# design.net
KiCad netlist of a schematic drawn in EasyEDA Pro
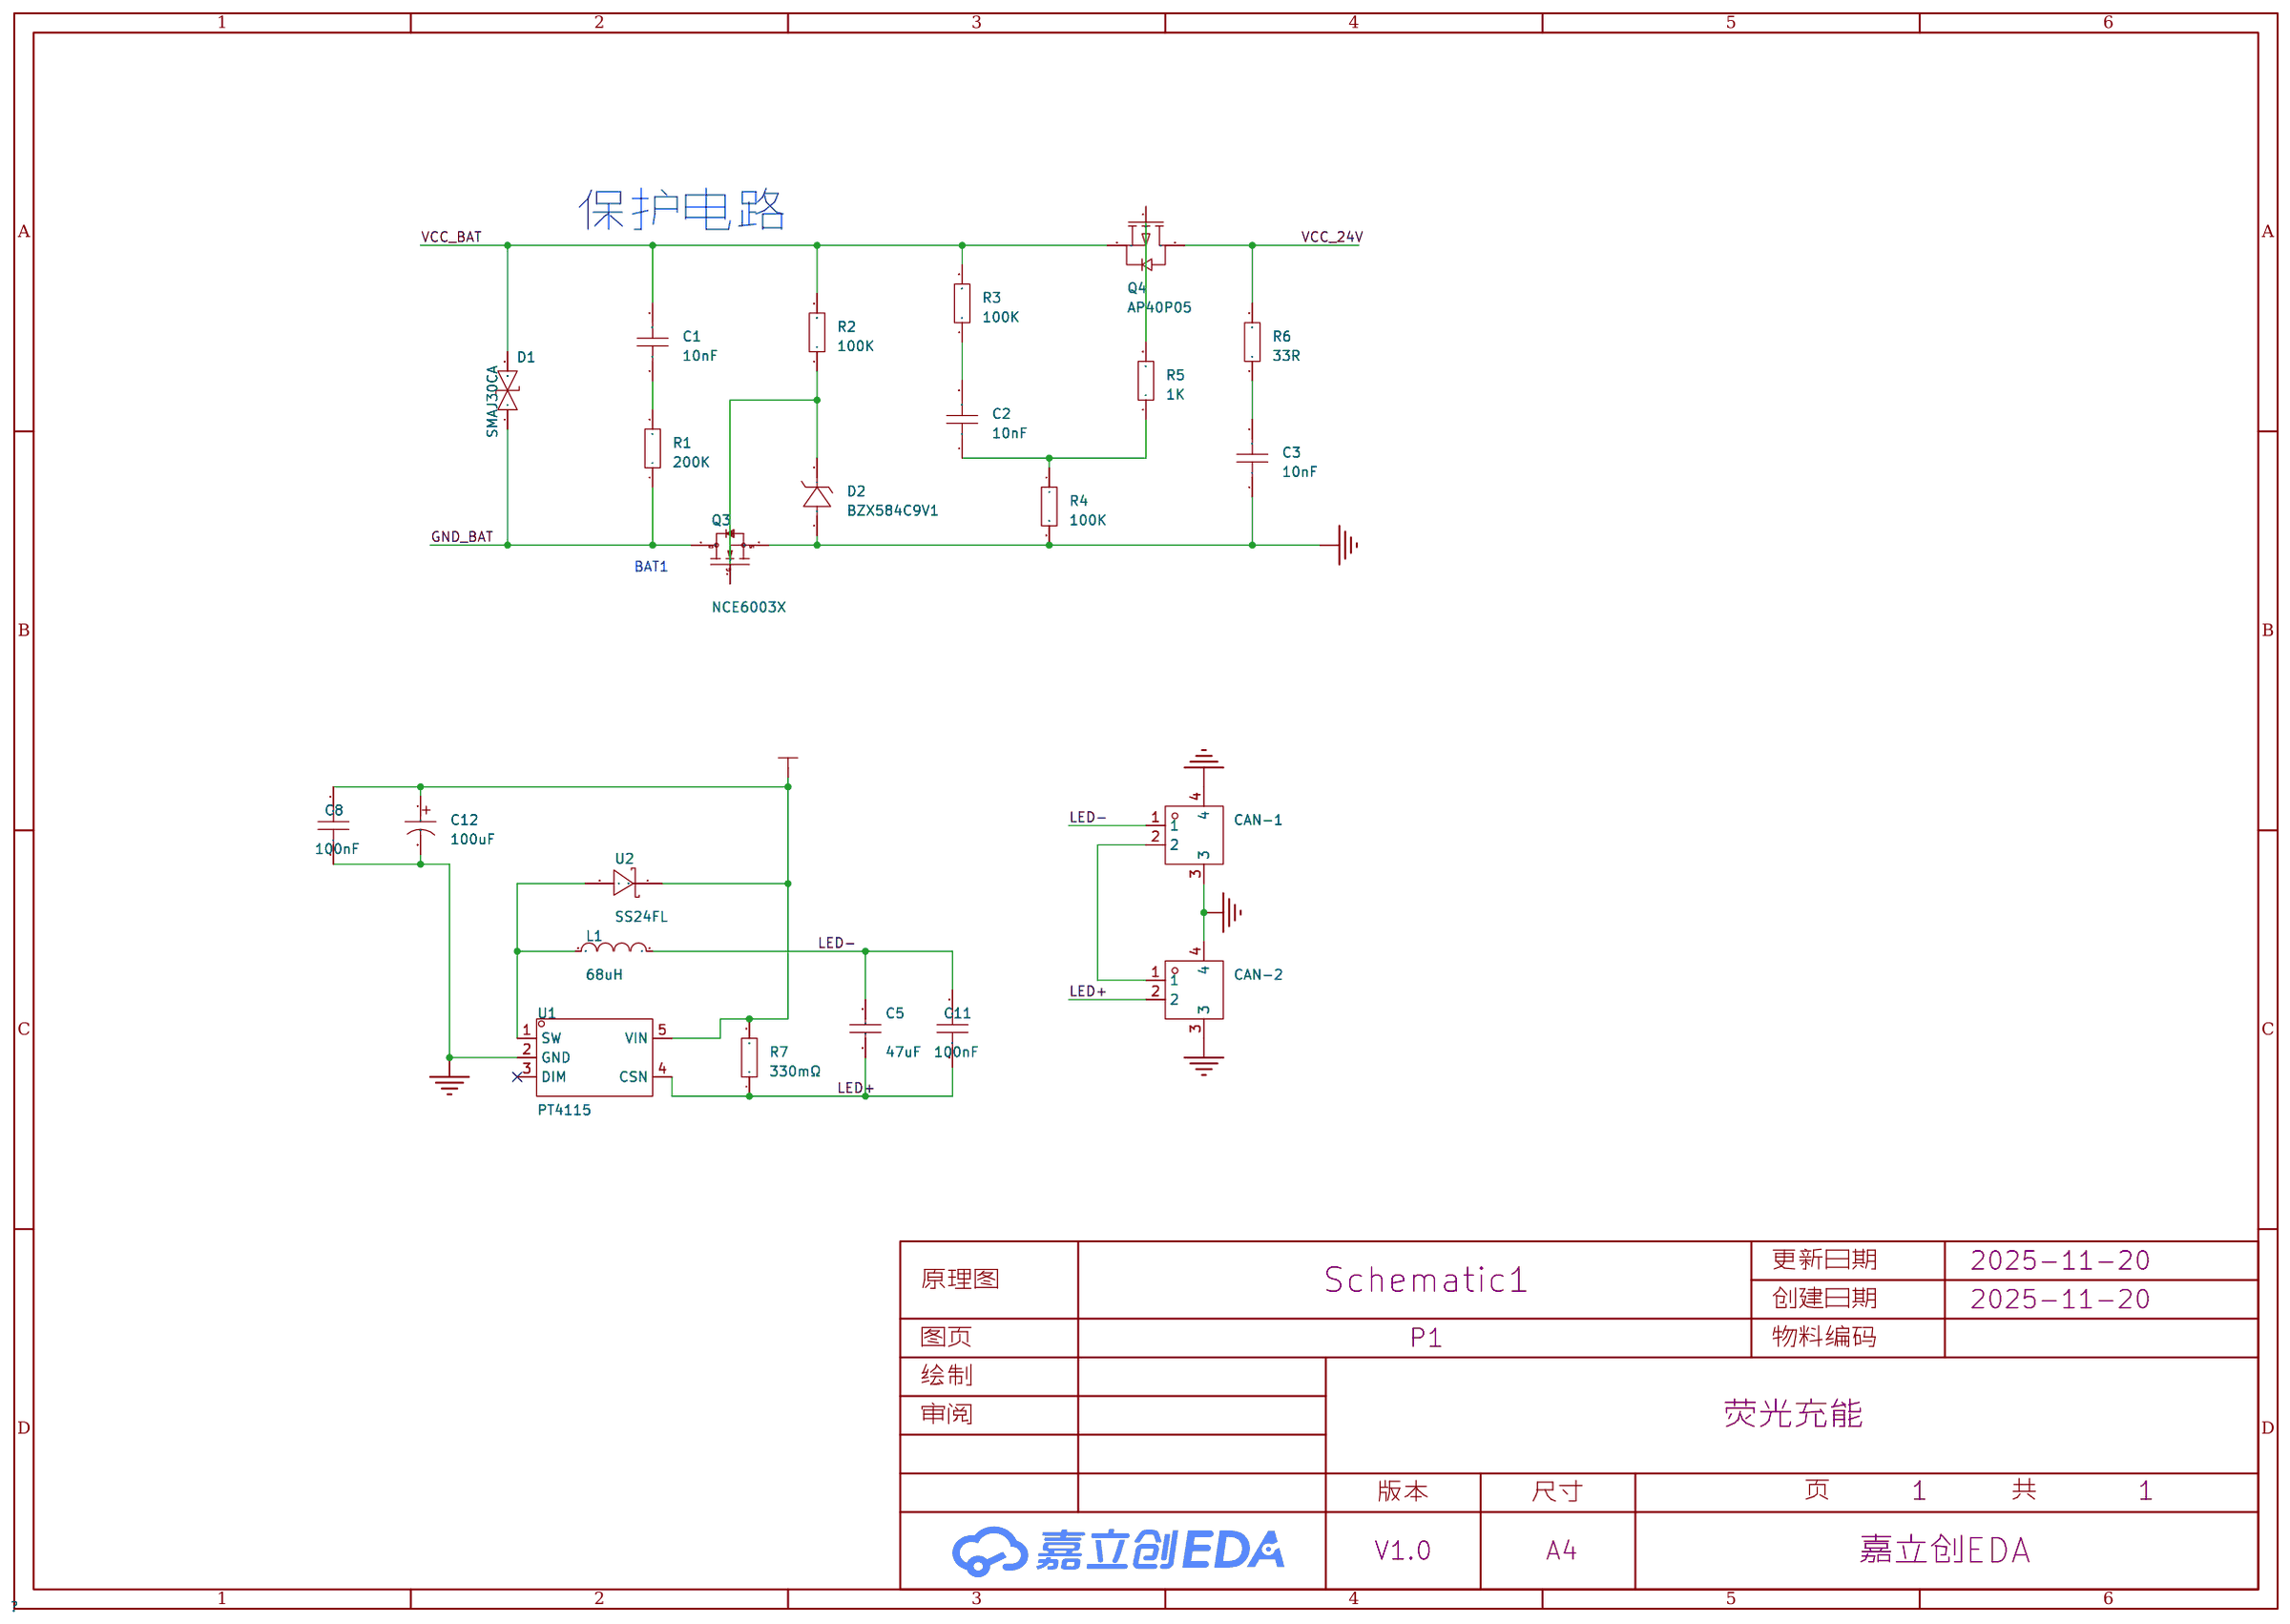
[diagram p0: schematic sheet]

(export (version "E")
  (design (tool "Eeschema 10.0.6"))
  (components
    (comp (ref "C1")
      (value "10nF")
      (footprint "easyedapro:C0603")
      (libsource (lib "easyedapro") (part "CapAcitance"))
    )
    (comp (ref "C2")
      (value "10nF")
      (footprint "easyedapro:C0603")
      (libsource (lib "easyedapro") (part "CapAcitance"))
    )
    (comp (ref "C3")
      (value "10nF")
      (footprint "easyedapro:C0603")
      (libsource (lib "easyedapro") (part "CapAcitance"))
    )
    (comp (ref "C5")
      (value "47uF")
      (footprint "easyedapro:C0805")
      (description "容值:1uF;精度:±10%;额定电压:50V;材质(温度系数):X7R;")
      (fields
        (field (name "Manufacturer Part") "CL21B105KBFNNNE")
        (field (name "Manufacturer") "SAMSUNG(三星)")
      )
      (libsource (lib "easyedapro") (part "CL21B105KBFNNNE"))
    )
    (comp (ref "C8")
      (value "100nF")
      (footprint "easyedapro:C0603")
      (description "容值:100nF;精度:±10%;额定电压:50V;温度系数:X7R;")
      (fields
        (field (name "Manufacturer Part") "CGA0603X7R104K500JT")
        (field (name "Manufacturer") "HRE(芯声)")
      )
      (libsource (lib "easyedapro") (part "CGA0603X7R104K500JT"))
    )
    (comp (ref "C11")
      (value "100nF")
      (footprint "easyedapro:C0603")
      (description "容值:100nF;精度:±10%;额定电压:50V;温度系数:X7R;")
      (fields
        (field (name "Manufacturer Part") "CGA0603X7R104K500JT")
        (field (name "Manufacturer") "HRE(芯声)")
      )
      (libsource (lib "easyedapro") (part "CGA0603X7R104K500JT"))
    )
    (comp (ref "C12")
      (value "100uF")
      (footprint "easyedapro:CAP-SMD_BD6.3-L6.6-W6.6-LS7.2-FD")
      (description "容值:100uF;精度:±20%;额定电压:35V;纹波电流:-;等效串联电阻(ESR):-;")
      (fields
        (field (name "Manufacturer Part") "HV101M035E077ETR")
        (field (name "Manufacturer") "CapXon(丰宾)")
      )
      (libsource (lib "easyedapro") (part "HV101M035E077R"))
    )
    (comp (ref "CAN-1")
      (value "X1251WVS-02HF-LPSW")
      (footprint "easyedapro:郭哥CAN2脚母接口")
      (fields (field (name "Manufacturer") "XKB Enterprise"))
      (libsource (lib "easyedapro") (part "X1251WVS-02HF-LPSW"))
    )
    (comp (ref "CAN-2")
      (value "X1251WVS-02HF-LPSW")
      (footprint "easyedapro:郭哥CAN2脚母接口")
      (fields (field (name "Manufacturer") "XKB Enterprise"))
      (libsource (lib "easyedapro") (part "X1251WVS-02HF-LPSW"))
    )
    (comp (ref "D1")
      (value "SMAJ30CA")
      (footprint "easyedapro:SMA_L4.4-W2.6-LS5.0-BI")
      (description "反向截止电压(Vrwm):30V;最大钳位电压:48.4V;峰值脉冲电流(Ipp)@10/1000us:8.3A;峰值脉冲功率(Ppp)@10/1000us:400W;击穿电压:33.3V;")
      (fields (field (name "Manufacturer") "MDD"))
      (libsource (lib "easyedapro") (part "SMAJ30CA-C110043"))
    )
    (comp (ref "D2")
      (value "BZX584C9V1")
      (footprint "easyedapro:SOD-523_L1.2-W0.8-LS1.6-FD")
      (description "二极管配置:独立式;稳压值(标称值):9.1V;稳压值(范围):8.5V~9.6V;功率:150mW;")
      (fields (field (name "Manufacturer") "宏迦橙"))
      (libsource (lib "easyedapro") (part "BZX584C9V1_C19077465"))
    )
    (comp (ref "L1")
      (value "68uH")
      (footprint "easyedapro:IND-SMD_L6.0-W6.0")
      (description "电感值:68uH;精度:±20%;额定电流:1A;")
      (fields (field (name "Manufacturer Part") "YNR6045-680M") (field (name "Manufacturer") "YJYCOIN(益嘉源)"))
      (libsource (lib "easyedapro") (part "YNR6045-680M"))
    )
    (comp (ref "Q3")
      (value "NCE6003X")
      (footprint "easyedapro:SOT-23-3_L2.9-W1.3-P1.90-LS2.4-BR")
      (description "类型:1个N沟道;漏源电压(Vdss):60V;功率(Pd):1.7W;阈值电压(Vgs(th)@Id):-;")
      (fields (field (name "Manufacturer") "NCE(无锡新洁能)"))
      (libsource (lib "easyedapro") (part "NCE6003X"))
    )
    (comp (ref "Q4")
      (value "AP40P05")
      (footprint "easyedapro:SOT-23-3_L2.9-W1.3-P1.90-LS2.4-BR")
      (description "类型:-;漏源电压(Vdss):40V;连续漏极电流(Id):5A;导通电阻(RDS(on)):85mΩ@10V;耗散功率(Pd):2W;阈值电压(Vgs(th)):1.6V;")
      (fields (field (name "Manufacturer") "ALLPOWER(铨力)"))
      (libsource (lib "easyedapro") (part "AP40P05"))
    )
    (comp (ref "R1") (value "200K") (footprint "easyedapro:R0603") (libsource (lib "easyedapro") (part "电阻")))
    (comp (ref "R2") (value "100K") (footprint "easyedapro:R0603") (libsource (lib "easyedapro") (part "电阻")))
    (comp (ref "R3") (value "100K") (footprint "easyedapro:R0603") (libsource (lib "easyedapro") (part "电阻")))
    (comp (ref "R4") (value "100K") (footprint "easyedapro:R0603") (libsource (lib "easyedapro") (part "电阻")))
    (comp (ref "R5") (value "1K") (footprint "easyedapro:R0603") (libsource (lib "easyedapro") (part "电阻")))
    (comp (ref "R6") (value "33R") (footprint "easyedapro:R0603") (libsource (lib "easyedapro") (part "电阻")))
    (comp (ref "R7")
      (value "330mΩ")
      (footprint "easyedapro:R1206")
      (description "电阻类型:厚膜电阻;阻值:330mΩ;精度:±1%;功率:250mW;最大工作电压:200V;温度系数:±800ppm/°C;")
      (fields
        (field (name "Manufacturer Part") "1206W4F330LT5E")
        (field (name "Manufacturer") "UNI-ROYAL(厚声)")
      )
      (libsource (lib "easyedapro") (part "1206W4F330LT5E"))
    )
    (comp (ref "U1")
      (value "PT4115")
      (footprint "easyedapro:SOT-89-5_L4.5-W2.5-P1.50-LS4.5-BR")
      (description "类型:-;输入电压:-;开关频率:-;通道数:-;输出电压:-;输出电流:-;调光:-;")
      (fields (field (name "Manufacturer") "UMW(友台半导体)"))
      (libsource (lib "easyedapro") (part "PT4115"))
    )
    (comp (ref "U2")
      (value "SS24FL")
      (footprint "easyedapro:SOD-123FL_L2.8-W1.8-LS3.6-RD")
      (description "正向压降(Vf):550mV@2A;直流反向耐压(Vr):40V;整流电流:2A;")
      (fields (field (name "Manufacturer") "onsemi(安森美)"))
      (libsource (lib "easyedapro") (part "SS24FL_C894433"))
    )
  )
  (nets
    (net (code "1") (name "/GND_BAT") (class "Default")
      (node (ref "D1") (pin "1") (pinfunction "1_1") (pintype "unspecified"))
      (node (ref "Q3") (pin "3") (pinfunction "D_3") (pintype "unspecified"))
      (node (ref "R1") (pin "1") (pinfunction "1_1") (pintype "input"))
    )
    (net (code "2") (name "/LED+") (class "Default")
      (node (ref "C11") (pin "1") (pinfunction "1_1") (pintype "unspecified"))
      (node (ref "C5") (pin "1") (pinfunction "1_1") (pintype "input"))
      (node (ref "CAN-2") (pin "2") (pinfunction "2_2") (pintype "unspecified"))
      (node (ref "R7") (pin "1") (pinfunction "1_1") (pintype "input"))
      (node (ref "U1") (pin "4") (pinfunction "CSN_4") (pintype "unspecified"))
    )
    (net (code "3") (name "/LED-") (class "Default")
      (node (ref "C11") (pin "2") (pinfunction "2_2") (pintype "unspecified"))
      (node (ref "C5") (pin "2") (pinfunction "2_2") (pintype "input"))
      (node (ref "CAN-1") (pin "1") (pinfunction "1_1") (pintype "unspecified"))
      (node (ref "L1") (pin "2") (pinfunction "2_2") (pintype "unspecified"))
    )
    (net (code "4") (name "/VCC_BAT") (class "Default")
      (node (ref "C1") (pin "2") (pinfunction "2_2") (pintype "input"))
      (node (ref "D1") (pin "2") (pinfunction "2_2") (pintype "unspecified"))
      (node (ref "Q4") (pin "2") (pinfunction "S_2") (pintype "unspecified"))
      (node (ref "R2") (pin "2") (pinfunction "2_2") (pintype "input"))
      (node (ref "R3") (pin "2") (pinfunction "2_2") (pintype "input"))
    )
    (net (code "5") (name "GND") (class "Default")
      (node (ref "C12") (pin "2") (pinfunction "2_2") (pintype "input"))
      (node (ref "C3") (pin "1") (pinfunction "1_1") (pintype "input"))
      (node (ref "C8") (pin "1") (pinfunction "1_1") (pintype "unspecified"))
      (node (ref "CAN-1") (pin "3") (pinfunction "3_3") (pintype "unspecified"))
      (node (ref "CAN-1") (pin "4") (pinfunction "4_4") (pintype "unspecified"))
      (node (ref "CAN-2") (pin "3") (pinfunction "3_3") (pintype "unspecified"))
      (node (ref "CAN-2") (pin "4") (pinfunction "4_4") (pintype "unspecified"))
      (node (ref "D2") (pin "1") (pinfunction "A_1") (pintype "unspecified"))
      (node (ref "Q3") (pin "2") (pinfunction "S_2") (pintype "unspecified"))
      (node (ref "R4") (pin "2") (pinfunction "2_2") (pintype "input"))
      (node (ref "U1") (pin "2") (pinfunction "GND_2") (pintype "unspecified"))
    )
    (net (code "6") (name "Net-(C1-Pad1)") (class "Default")
      (node (ref "C1") (pin "1") (pinfunction "1_1") (pintype "input"))
      (node (ref "R1") (pin "2") (pinfunction "2_2") (pintype "input"))
    )
    (net (code "7") (name "Net-(C2-Pad1)") (class "Default")
      (node (ref "C2") (pin "1") (pinfunction "1_1") (pintype "input"))
      (node (ref "R4") (pin "1") (pinfunction "1_1") (pintype "input"))
      (node (ref "R5") (pin "1") (pinfunction "1_1") (pintype "input"))
    )
    (net (code "8") (name "Net-(C2-Pad2)") (class "Default")
      (node (ref "C2") (pin "2") (pinfunction "2_2") (pintype "input"))
      (node (ref "R3") (pin "1") (pinfunction "1_1") (pintype "input"))
    )
    (net (code "9") (name "Net-(C3-Pad2)") (class "Default")
      (node (ref "C3") (pin "2") (pinfunction "2_2") (pintype "input"))
      (node (ref "R6") (pin "1") (pinfunction "1_1") (pintype "input"))
    )
    (net (code "10") (name "Net-(CAN-1-Pad2)") (class "Default")
      (node (ref "CAN-1") (pin "2") (pinfunction "2_2") (pintype "unspecified"))
      (node (ref "CAN-2") (pin "1") (pinfunction "1_1") (pintype "unspecified"))
    )
    (net (code "11") (name "Net-(D2-K)") (class "Default")
      (node (ref "D2") (pin "2") (pinfunction "K_2") (pintype "unspecified"))
      (node (ref "Q3") (pin "1") (pinfunction "G_1") (pintype "unspecified"))
      (node (ref "R2") (pin "1") (pinfunction "1_1") (pintype "input"))
    )
    (net (code "12") (name "Net-(Q4-G)") (class "Default")
      (node (ref "Q4") (pin "1") (pinfunction "G_1") (pintype "unspecified"))
      (node (ref "R5") (pin "2") (pinfunction "2_2") (pintype "input"))
    )
    (net (code "13") (name "Net-(U1-SW)") (class "Default")
      (node (ref "L1") (pin "1") (pinfunction "1_1") (pintype "unspecified"))
      (node (ref "U1") (pin "1") (pinfunction "SW_1") (pintype "unspecified"))
      (node (ref "U2") (pin "2") (pinfunction "A_2") (pintype "unspecified"))
    )
    (net (code "14") (name "VCC_24V") (class "Default")
      (node (ref "C12") (pin "1") (pinfunction "1_1") (pintype "input"))
      (node (ref "C8") (pin "2") (pinfunction "2_2") (pintype "unspecified"))
      (node (ref "Q4") (pin "3") (pinfunction "D_3") (pintype "unspecified"))
      (node (ref "R6") (pin "2") (pinfunction "2_2") (pintype "input"))
      (node (ref "R7") (pin "2") (pinfunction "2_2") (pintype "input"))
      (node (ref "U1") (pin "5") (pinfunction "VIN_5") (pintype "unspecified"))
      (node (ref "U2") (pin "1") (pinfunction "C_1") (pintype "unspecified"))
    )
    (net (code "15") (name "unconnected-(U1-DIM-Pad3)") (class "Default")
      (node (ref "U1") (pin "3") (pinfunction "DIM_3") (pintype "unspecified+no_connect"))
    )
  )
)
